# ultrasonic_sensor.net
KiCad netlist of a schematic drawn in EAGLE
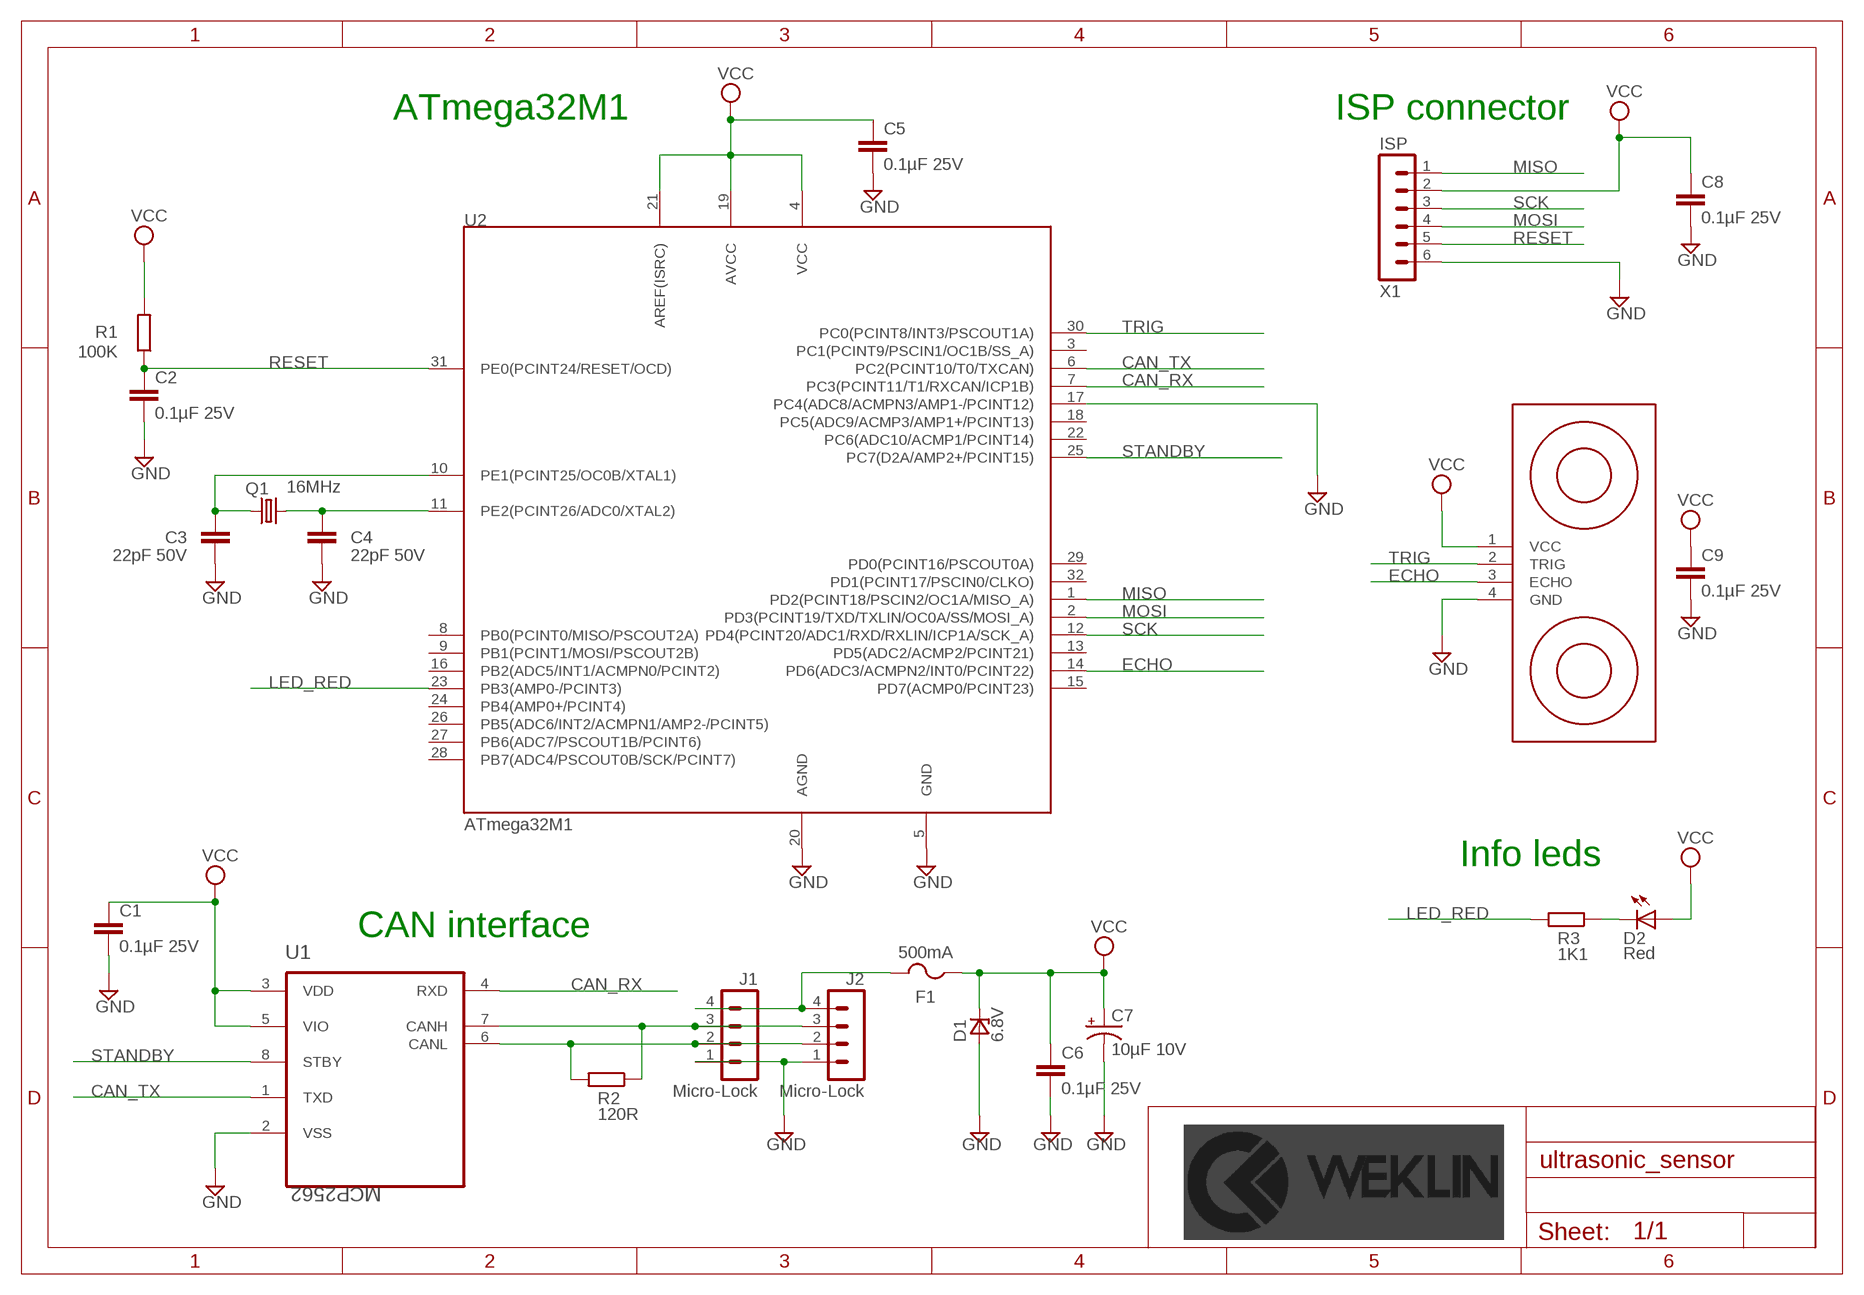
[diagram p0: schematic, sheet 1]

(export (version "E")
  (design (tool "Eeschema 10.0.6"))
  (components
    (comp (ref "C1")
      (value "0.1µF 25V")
      (footprint "eagle-import:C2012")
      (fields (field (name "MANUFACTURER") "AVX") (field (name "MPN") "08053C104KAT2A"))
      (libsource (lib "eagle-import") (part "CAPACITOR_NON_POL-0.1µF-25V(+-10%)(2012)"))
    )
    (comp (ref "C2")
      (value "0.1µF 25V")
      (footprint "eagle-import:C2012")
      (fields (field (name "MANUFACTURER") "AVX") (field (name "MPN") "08053C104KAT2A"))
      (libsource (lib "eagle-import") (part "CAPACITOR_NON_POL-0.1µF-25V(+-10%)(2012)"))
    )
    (comp (ref "C3")
      (value "22pF 50V")
      (footprint "eagle-import:C2012")
      (fields (field (name "MANUFACTURER") "Multicomp") (field (name "MPN") "MC0805N220J500CT"))
      (libsource (lib "eagle-import") (part "CAPACITOR_NON_POL-22PF-50V(+-5%)(2012)"))
    )
    (comp (ref "C4")
      (value "22pF 50V")
      (footprint "eagle-import:C2012")
      (fields (field (name "MANUFACTURER") "Multicomp") (field (name "MPN") "MC0805N220J500CT"))
      (libsource (lib "eagle-import") (part "CAPACITOR_NON_POL-22PF-50V(+-5%)(2012)"))
    )
    (comp (ref "C5")
      (value "0.1µF 25V")
      (footprint "eagle-import:C2012")
      (fields (field (name "MANUFACTURER") "AVX") (field (name "MPN") "08053C104KAT2A"))
      (libsource (lib "eagle-import") (part "CAPACITOR_NON_POL-0.1µF-25V(+-10%)(2012)"))
    )
    (comp (ref "C6")
      (value "0.1µF 25V")
      (footprint "eagle-import:C2012")
      (fields (field (name "MANUFACTURER") "AVX") (field (name "MPN") "08053C104KAT2A"))
      (libsource (lib "eagle-import") (part "CAPACITOR_NON_POL-0.1µF-25V(+-10%)(2012)"))
    )
    (comp (ref "C7")
      (value "10µF 10V")
      (footprint "eagle-import:EIA3216")
      (fields (field (name "MANUFACTURER") "Kemet") (field (name "MPN") "T491A106K010AT"))
      (libsource (lib "eagle-import") (part "CAPACITOR_POL-10µF-10V(+-10%)(3216)"))
    )
    (comp (ref "C8")
      (value "0.1µF 25V")
      (footprint "eagle-import:C2012")
      (fields (field (name "MANUFACTURER") "AVX") (field (name "MPN") "08053C104KAT2A"))
      (libsource (lib "eagle-import") (part "CAPACITOR_NON_POL-0.1µF-25V(+-10%)(2012)"))
    )
    (comp (ref "C9")
      (value "0.1µF 25V")
      (footprint "eagle-import:C2012")
      (fields (field (name "MANUFACTURER") "AVX") (field (name "MPN") "08053C104KAT2A"))
      (libsource (lib "eagle-import") (part "CAPACITOR_NON_POL-0.1µF-25V(+-10%)(2012)"))
    )
    (comp (ref "D1")
      (value "6.8V")
      (footprint "eagle-import:DO-214AA")
      (fields (field (name "MANUFACTURER") "ON Semiconductor") (field (name "MPN") "P6SMB6.8AT3G"))
      (libsource (lib "eagle-import") (part "ZENER_UNIDIR6.8"))
    )
    (comp (ref "D2")
      (value "Red")
      (footprint "eagle-import:VLD")
      (fields (field (name "MANUFACTURER") "Vishay") (field (name "MPN") "VLDS1235G"))
      (libsource (lib "eagle-import") (part "LEDVLDS1235G"))
    )
    (comp (ref "F1")
      (value "500mA")
      (footprint "eagle-import:EIARS-481-2")
      (fields (field (name "MANUFACTURER") "Littlefuse") (field (name "MPN") "0451.500MRL"))
      (libsource (lib "eagle-import") (part "FUSE"))
    )
    (comp (ref "J1")
      (value "Micro-Lock")
      (footprint "eagle-import:504195-0470")
      (fields (field (name "MANUFACTURER") "Molex") (field (name "MPN") "504195-0470"))
      (libsource (lib "eagle-import") (part "MICROLOCK-4CMS"))
    )
    (comp (ref "J2")
      (value "Micro-Lock")
      (footprint "eagle-import:504195-0470")
      (fields (field (name "MANUFACTURER") "Molex") (field (name "MPN") "504195-0470"))
      (libsource (lib "eagle-import") (part "MICROLOCK-4CMS"))
    )
    (comp (ref "Q1")
      (value "16MHz")
      (footprint "eagle-import:SMD_KX7")
      (fields (field (name "MANUFACTURER") "AEL CRYSTALS") (field (name "MPN") "E3SB16.0000F09G11AE"))
      (libsource (lib "eagle-import") (part "CRYSTAL-16MHZ_SMD(3225)"))
    )
    (comp (ref "R1")
      (value "100K")
      (footprint "eagle-import:R2012")
      (fields (field (name "MANUFACTURER") "Multicomp") (field (name "MPN") "MCWR08X1003FTL"))
      (libsource (lib "eagle-import") (part "RESISTOR-100K(+-1%)(2012)"))
    )
    (comp (ref "R2")
      (value "120R")
      (footprint "eagle-import:R2012")
      (fields (field (name "MANUFACTURER") "Multicomp") (field (name "MPN") "MCWR08X1200FTL"))
      (libsource (lib "eagle-import") (part "RESISTOR-120R(+-1%)(2012)"))
    )
    (comp (ref "R3")
      (value "1K1")
      (footprint "eagle-import:R2012")
      (fields (field (name "MANUFACTURER") "Multicomp") (field (name "MPN") "MC0805S8F1101T5E"))
      (libsource (lib "eagle-import") (part "RESISTOR-1K1(+-1%)(2012)"))
    )
    (comp (ref "U1")
      (value "MCP2562")
      (footprint "eagle-import:SOIC8")
      (fields (field (name "MANUFACTURER") "Microchip") (field (name "MPN") "MCP2562-E/SN"))
      (libsource (lib "eagle-import") (part "MCP2562-E/SN-SOIC8"))
    )
    (comp (ref "U2")
      (value "ATmega32M1")
      (footprint "eagle-import:TQFP32")
      (fields (field (name "MANUFACTURER") "Atmel") (field (name "MPN") "ATmega32M1-AU"))
      (libsource (lib "eagle-import") (part "ATMEGA32M1-TQFP32"))
    )
    (comp (ref "U3")
      (value "HC-SR04")
      (footprint "eagle-import:ULTRASONIC-HC-SR04")
      (fields (field (name "MANUFACTURER") "Unknow"))
      (libsource (lib "eagle-import") (part "ULTRASONIC-HC-SR04"))
    )
    (comp (ref "X1")
      (value "ISP")
      (footprint "eagle-import:MINITEK_127_6WAY_SMD")
      (fields (field (name "MANUFACTURER") "Minitek") (field (name "MPN") "20021121-00006C4LF"))
      (libsource (lib "eagle-import") (part "MINITEK_127_6WAYS-SMD"))
    )
  )
  (nets
    (net (code "1") (name "/CAN_RX") (class "Default")
      (node (ref "U1") (pin "4") (pinfunction "RXD_4") (pintype "output"))
      (node (ref "U2") (pin "7") (pinfunction "PC3(PCINT11/T1/RXCAN/ICP1B)_7") (pintype "bidirectional"))
    )
    (net (code "2") (name "/CAN_TX") (class "Default")
      (node (ref "U1") (pin "1") (pinfunction "TXD_1") (pintype "input"))
      (node (ref "U2") (pin "6") (pinfunction "PC2(PCINT10/T0/TXCAN)_6") (pintype "bidirectional"))
    )
    (net (code "3") (name "/ECHO") (class "Default")
      (node (ref "U2") (pin "14") (pinfunction "PD6(ADC3/ACMPN2/INT0/PCINT22)_14") (pintype "bidirectional"))
      (node (ref "U3") (pin "3") (pinfunction "ECHO_3") (pintype "output"))
    )
    (net (code "4") (name "/LED_RED") (class "Default")
      (node (ref "R3") (pin "2") (pinfunction "2_2") (pintype "passive"))
      (node (ref "U2") (pin "23") (pinfunction "PB3(AMP0-/PCINT3)_23") (pintype "bidirectional"))
    )
    (net (code "5") (name "/MISO") (class "Default")
      (node (ref "U2") (pin "1") (pinfunction "PD2(PCINT18/PSCIN2/OC1A/MISO_A)_1") (pintype "bidirectional"))
      (node (ref "X1") (pin "1") (pinfunction "1_1") (pintype "passive"))
    )
    (net (code "6") (name "/MOSI") (class "Default")
      (node (ref "U2") (pin "2") (pinfunction "PD3(PCINT19/TXD/TXLIN/OC0A/SS/MOSI_A)_2") (pintype "bidirectional"))
      (node (ref "X1") (pin "4") (pinfunction "4_4") (pintype "passive"))
    )
    (net (code "7") (name "/RESET") (class "Default")
      (node (ref "C2") (pin "1") (pinfunction "1_1") (pintype "passive"))
      (node (ref "R1") (pin "1") (pinfunction "1_1") (pintype "passive"))
      (node (ref "U2") (pin "31") (pinfunction "PE0(PCINT24/RESET/OCD)_31") (pintype "bidirectional"))
      (node (ref "X1") (pin "5") (pinfunction "5_5") (pintype "passive"))
    )
    (net (code "8") (name "/SCK") (class "Default")
      (node (ref "U2") (pin "12") (pinfunction "PD4(PCINT20/ADC1/RXD/RXLIN/ICP1A/SCK_A)_12") (pintype "bidirectional"))
      (node (ref "X1") (pin "3") (pinfunction "3_3") (pintype "passive"))
    )
    (net (code "9") (name "/STANDBY") (class "Default")
      (node (ref "U1") (pin "8") (pinfunction "STBY_8") (pintype "input"))
      (node (ref "U2") (pin "25") (pinfunction "PC7(D2A/AMP2+/PCINT15)_25") (pintype "bidirectional"))
    )
    (net (code "10") (name "/TRIG") (class "Default")
      (node (ref "U2") (pin "30") (pinfunction "PC0(PCINT8/INT3/PSCOUT1A)_30") (pintype "bidirectional"))
      (node (ref "U3") (pin "2") (pinfunction "TRIG_2") (pintype "input"))
    )
    (net (code "11") (name "GND") (class "Default")
      (node (ref "C1") (pin "2") (pinfunction "2_2") (pintype "passive"))
      (node (ref "C2") (pin "2") (pinfunction "2_2") (pintype "passive"))
      (node (ref "C3") (pin "2") (pinfunction "2_2") (pintype "passive"))
      (node (ref "C4") (pin "2") (pinfunction "2_2") (pintype "passive"))
      (node (ref "C5") (pin "2") (pinfunction "2_2") (pintype "passive"))
      (node (ref "C6") (pin "2") (pinfunction "2_2") (pintype "passive"))
      (node (ref "C7") (pin "C") (pinfunction "-_C") (pintype "passive"))
      (node (ref "C8") (pin "2") (pinfunction "2_2") (pintype "passive"))
      (node (ref "C9") (pin "2") (pinfunction "2_2") (pintype "passive"))
      (node (ref "D1") (pin "A") (pinfunction "A_A") (pintype "passive"))
      (node (ref "J1") (pin "1") (pinfunction "1_1") (pintype "passive"))
      (node (ref "J2") (pin "1") (pinfunction "1_1") (pintype "passive"))
      (node (ref "U1") (pin "2") (pinfunction "VSS_2") (pintype "power_in"))
      (node (ref "U2") (pin "17") (pinfunction "PC4(ADC8/ACMPN3/AMP1-/PCINT12)_17") (pintype "bidirectional"))
      (node (ref "U2") (pin "20") (pinfunction "AGND_20") (pintype "power_in"))
      (node (ref "U2") (pin "5") (pinfunction "GND_5") (pintype "power_in"))
      (node (ref "U3") (pin "4") (pinfunction "GND_4") (pintype "power_in"))
      (node (ref "X1") (pin "6") (pinfunction "6_6") (pintype "passive"))
    )
    (net (code "12") (name "Net-(D2-PadC)") (class "Default")
      (node (ref "D2") (pin "C") (pinfunction "C_C") (pintype "passive"))
      (node (ref "R3") (pin "1") (pinfunction "1_1") (pintype "passive"))
    )
    (net (code "13") (name "Net-(F1-Pad2)") (class "Default")
      (node (ref "F1") (pin "2") (pinfunction "2_2") (pintype "passive"))
      (node (ref "J1") (pin "4") (pinfunction "4_4") (pintype "passive"))
      (node (ref "J2") (pin "4") (pinfunction "4_4") (pintype "passive"))
    )
    (net (code "14") (name "Net-(Q1-2)") (class "Default")
      (node (ref "C4") (pin "1") (pinfunction "1_1") (pintype "passive"))
      (node (ref "Q1") (pin "3") (pinfunction "2_3") (pintype "passive"))
      (node (ref "U2") (pin "11") (pinfunction "PE2(PCINT26/ADC0/XTAL2)_11") (pintype "bidirectional"))
    )
    (net (code "15") (name "Net-(U1-CANH)") (class "Default")
      (node (ref "J1") (pin "3") (pinfunction "3_3") (pintype "passive"))
      (node (ref "J2") (pin "3") (pinfunction "3_3") (pintype "passive"))
      (node (ref "R2") (pin "1") (pinfunction "1_1") (pintype "passive"))
      (node (ref "U1") (pin "7") (pinfunction "CANH_7") (pintype "bidirectional"))
    )
    (net (code "16") (name "Net-(U1-CANL)") (class "Default")
      (node (ref "J1") (pin "2") (pinfunction "2_2") (pintype "passive"))
      (node (ref "J2") (pin "2") (pinfunction "2_2") (pintype "passive"))
      (node (ref "R2") (pin "2") (pinfunction "2_2") (pintype "passive"))
      (node (ref "U1") (pin "6") (pinfunction "CANL_6") (pintype "bidirectional"))
    )
    (net (code "17") (name "Net-(U2-PE1(PCINT25{slash}OC0B{slash}XTAL1))") (class "Default")
      (node (ref "C3") (pin "1") (pinfunction "1_1") (pintype "passive"))
      (node (ref "Q1") (pin "1") (pinfunction "1_1") (pintype "passive"))
      (node (ref "U2") (pin "10") (pinfunction "PE1(PCINT25/OC0B/XTAL1)_10") (pintype "bidirectional"))
    )
    (net (code "18") (name "VCC") (class "Default")
      (node (ref "C1") (pin "1") (pinfunction "1_1") (pintype "passive"))
      (node (ref "C5") (pin "1") (pinfunction "1_1") (pintype "passive"))
      (node (ref "C6") (pin "1") (pinfunction "1_1") (pintype "passive"))
      (node (ref "C7") (pin "A") (pinfunction "+_A") (pintype "passive"))
      (node (ref "C8") (pin "1") (pinfunction "1_1") (pintype "passive"))
      (node (ref "C9") (pin "1") (pinfunction "1_1") (pintype "passive"))
      (node (ref "D1") (pin "C") (pinfunction "C_C") (pintype "passive"))
      (node (ref "D2") (pin "A") (pinfunction "A_A") (pintype "passive"))
      (node (ref "F1") (pin "1") (pinfunction "1_1") (pintype "passive"))
      (node (ref "R1") (pin "2") (pinfunction "2_2") (pintype "passive"))
      (node (ref "U1") (pin "3") (pinfunction "VDD_3") (pintype "power_in"))
      (node (ref "U1") (pin "5") (pinfunction "VIO_5") (pintype "power_in"))
      (node (ref "U2") (pin "19") (pinfunction "AVCC_19") (pintype "power_in"))
      (node (ref "U2") (pin "21") (pinfunction "AREF(ISRC)_21") (pintype "power_in"))
      (node (ref "U2") (pin "4") (pinfunction "VCC_4") (pintype "power_in"))
      (node (ref "U3") (pin "1") (pinfunction "VCC_1") (pintype "power_in"))
      (node (ref "X1") (pin "2") (pinfunction "2_2") (pintype "passive"))
    )
    (net (code "19") (name "unconnected-(U2-PB0(PCINT0{slash}MISO{slash}PSCOUT2A)-Pad8)") (class "Default")
      (node (ref "U2") (pin "8") (pinfunction "PB0(PCINT0/MISO/PSCOUT2A)_8") (pintype "bidirectional"))
    )
    (net (code "20") (name "unconnected-(U2-PB1(PCINT1{slash}MOSI{slash}PSCOUT2B)-Pad9)") (class "Default")
      (node (ref "U2") (pin "9") (pinfunction "PB1(PCINT1/MOSI/PSCOUT2B)_9") (pintype "bidirectional"))
    )
    (net (code "21") (name "unconnected-(U2-PB2(ADC5{slash}INT1{slash}ACMPN0{slash}PCINT2)-Pad16)") (class "Default")
      (node (ref "U2") (pin "16") (pinfunction "PB2(ADC5/INT1/ACMPN0/PCINT2)_16") (pintype "bidirectional"))
    )
    (net (code "22") (name "unconnected-(U2-PB4(AMP0+{slash}PCINT4)-Pad24)") (class "Default")
      (node (ref "U2") (pin "24") (pinfunction "PB4(AMP0+/PCINT4)_24") (pintype "bidirectional"))
    )
    (net (code "23") (name "unconnected-(U2-PB5(ADC6{slash}INT2{slash}ACMPN1{slash}AMP2-{slash}PCINT5)-Pad26)") (class "Default")
      (node (ref "U2") (pin "26") (pinfunction "PB5(ADC6/INT2/ACMPN1/AMP2-/PCINT5)_26") (pintype "bidirectional"))
    )
    (net (code "24") (name "unconnected-(U2-PB6(ADC7{slash}PSCOUT1B{slash}PCINT6)-Pad27)") (class "Default")
      (node (ref "U2") (pin "27") (pinfunction "PB6(ADC7/PSCOUT1B/PCINT6)_27") (pintype "bidirectional"))
    )
    (net (code "25") (name "unconnected-(U2-PB7(ADC4{slash}PSCOUT0B{slash}SCK{slash}PCINT7)-Pad28)") (class "Default")
      (node (ref "U2") (pin "28") (pinfunction "PB7(ADC4/PSCOUT0B/SCK/PCINT7)_28") (pintype "bidirectional"))
    )
    (net (code "26") (name "unconnected-(U2-PC1(PCINT9{slash}PSCIN1{slash}OC1B{slash}SS_A)-Pad3)") (class "Default")
      (node (ref "U2") (pin "3") (pinfunction "PC1(PCINT9/PSCIN1/OC1B/SS_A)_3") (pintype "bidirectional"))
    )
    (net (code "27") (name "unconnected-(U2-PC5(ADC9{slash}ACMP3{slash}AMP1+{slash}PCINT13)-Pad18)") (class "Default")
      (node (ref "U2") (pin "18") (pinfunction "PC5(ADC9/ACMP3/AMP1+/PCINT13)_18") (pintype "bidirectional"))
    )
    (net (code "28") (name "unconnected-(U2-PC6(ADC10{slash}ACMP1{slash}PCINT14)-Pad22)") (class "Default")
      (node (ref "U2") (pin "22") (pinfunction "PC6(ADC10/ACMP1/PCINT14)_22") (pintype "bidirectional"))
    )
    (net (code "29") (name "unconnected-(U2-PD0(PCINT16{slash}PSCOUT0A)-Pad29)") (class "Default")
      (node (ref "U2") (pin "29") (pinfunction "PD0(PCINT16/PSCOUT0A)_29") (pintype "bidirectional"))
    )
    (net (code "30") (name "unconnected-(U2-PD1(PCINT17{slash}PSCIN0{slash}CLKO)-Pad32)") (class "Default")
      (node (ref "U2") (pin "32") (pinfunction "PD1(PCINT17/PSCIN0/CLKO)_32") (pintype "bidirectional"))
    )
    (net (code "31") (name "unconnected-(U2-PD5(ADC2{slash}ACMP2{slash}PCINT21)-Pad13)") (class "Default")
      (node (ref "U2") (pin "13") (pinfunction "PD5(ADC2/ACMP2/PCINT21)_13") (pintype "bidirectional"))
    )
    (net (code "32") (name "unconnected-(U2-PD7(ACMP0{slash}PCINT23)-Pad15)") (class "Default")
      (node (ref "U2") (pin "15") (pinfunction "PD7(ACMP0/PCINT23)_15") (pintype "bidirectional"))
    )
  )
)
